# Board.net
KiCad netlist of a schematic drawn in EAGLE
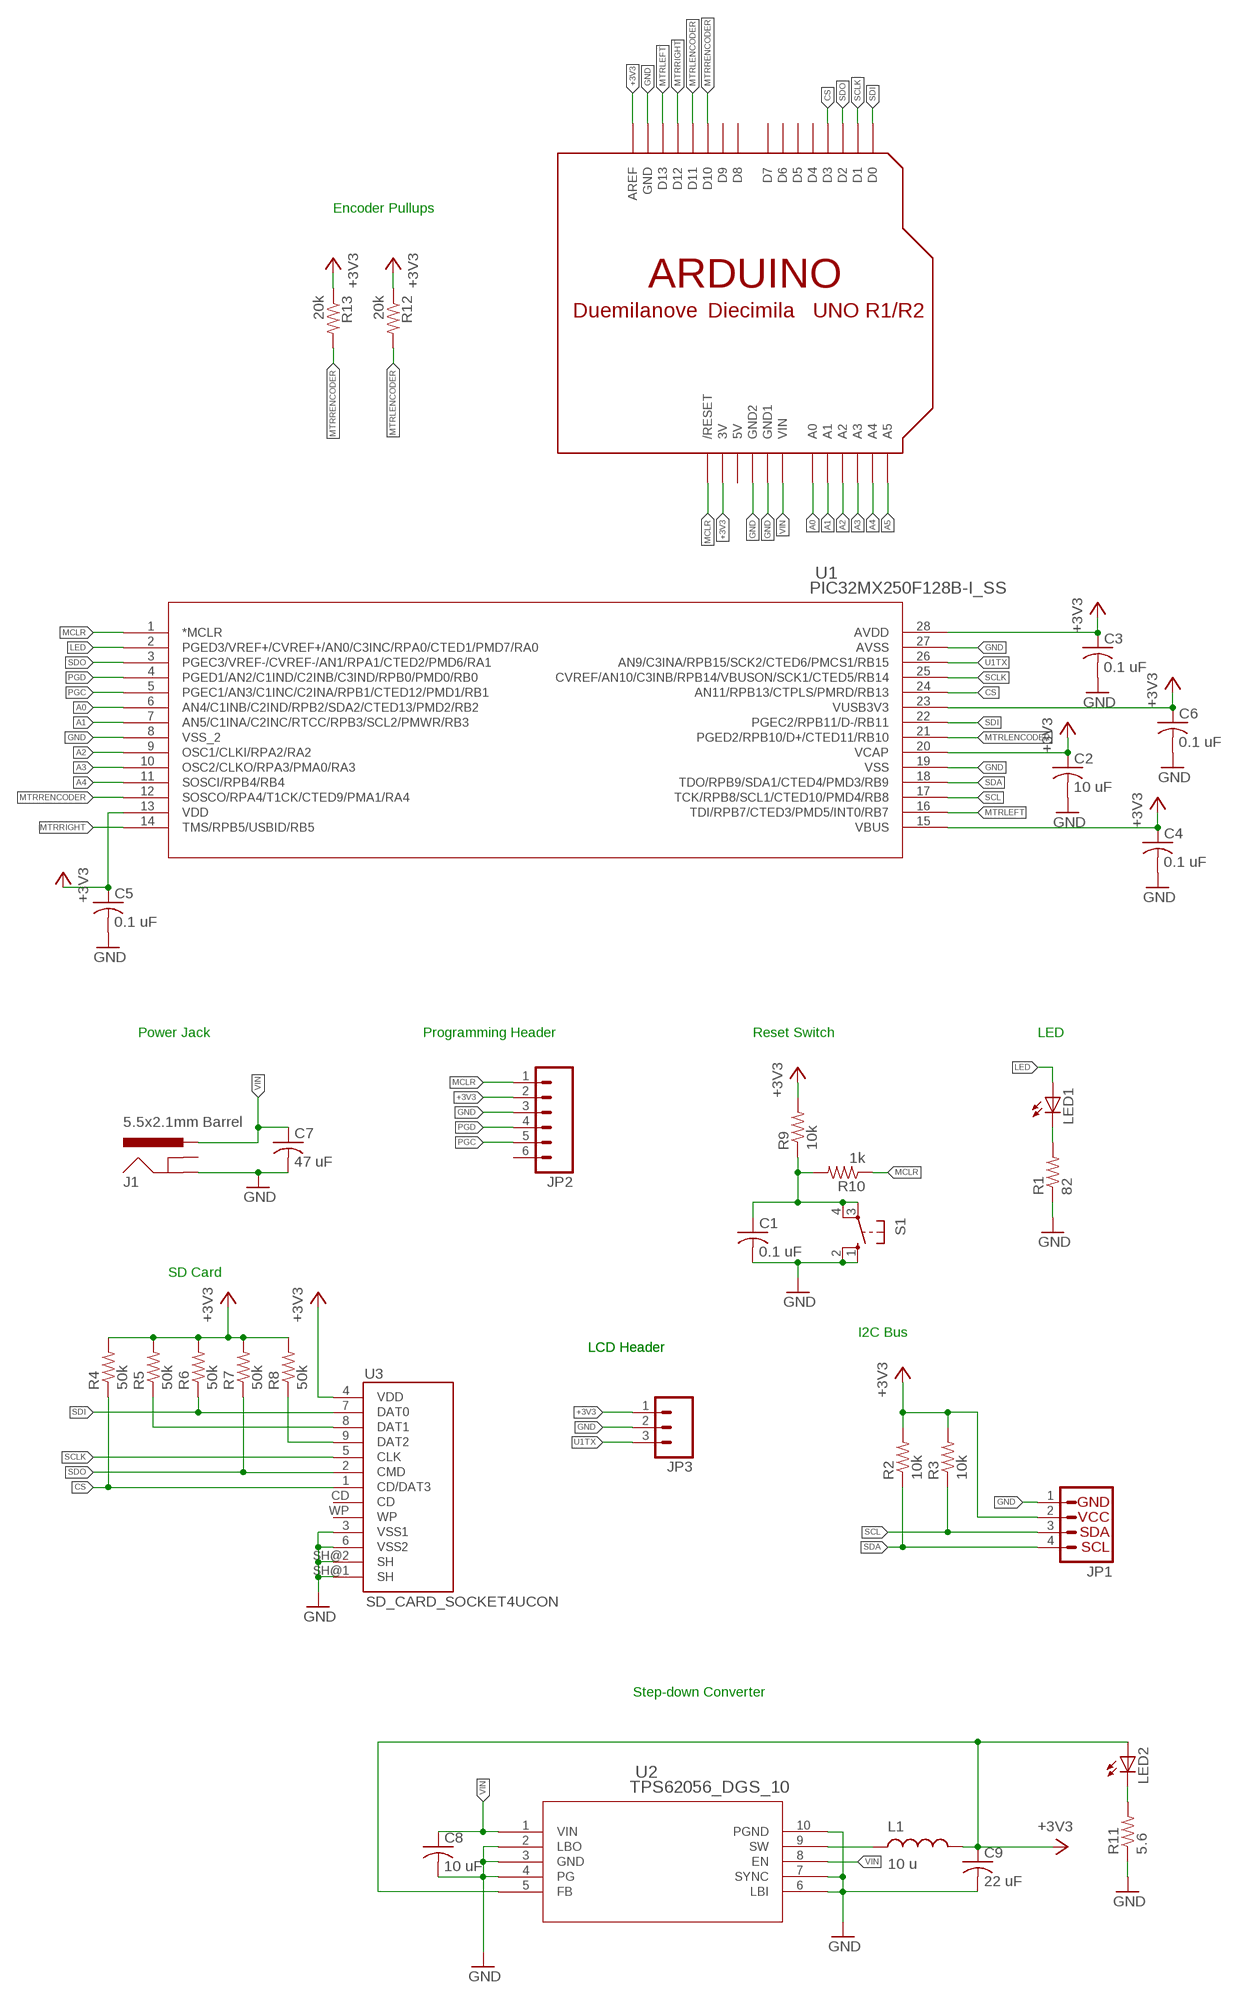
[diagram p0: schematic, sheet 1]

(export (version "E")
  (design (tool "Eeschema 10.0.6"))
  (components
    (comp (ref "C1")
      (value "0.1 uF")
      (footprint "eagle-import:C0805")
      (libsource (lib "eagle-import") (part "C-USC0805"))
    )
    (comp (ref "C2")
      (value "10 uF")
      (footprint "eagle-import:C0805")
      (libsource (lib "eagle-import") (part "C-USC0805"))
    )
    (comp (ref "C3")
      (value "0.1 uF")
      (footprint "eagle-import:C0805")
      (libsource (lib "eagle-import") (part "C-USC0805"))
    )
    (comp (ref "C4")
      (value "0.1 uF")
      (footprint "eagle-import:C0805")
      (libsource (lib "eagle-import") (part "C-USC0805"))
    )
    (comp (ref "C5")
      (value "0.1 uF")
      (footprint "eagle-import:C0805")
      (libsource (lib "eagle-import") (part "C-USC0805"))
    )
    (comp (ref "C6")
      (value "0.1 uF")
      (footprint "eagle-import:C0805")
      (libsource (lib "eagle-import") (part "C-USC0805"))
    )
    (comp (ref "C7")
      (value "47 uF")
      (footprint "eagle-import:C0805")
      (libsource (lib "eagle-import") (part "C-USC0805"))
    )
    (comp (ref "C8")
      (value "10 uF")
      (footprint "eagle-import:C0805")
      (libsource (lib "eagle-import") (part "C-USC0805"))
    )
    (comp (ref "C9")
      (value "22 uF")
      (footprint "eagle-import:C0805")
      (libsource (lib "eagle-import") (part "C-USC0805"))
    )
    (comp (ref "J1")
      (value "5.5x2.1mm Barrel")
      (footprint "eagle-import:POWER_JACK_SMD")
      (libsource (lib "eagle-import") (part "POWER_JACKSMD"))
    )
    (comp (ref "JP1")
      (value "I2C_STANDARD")
      (footprint "eagle-import:1X04")
      (libsource (lib "eagle-import") (part "I2C_STANDARD"))
    )
    (comp (ref "JP2")
      (value "M06SILK_FEMALE_PTH")
      (footprint "eagle-import:1X06")
      (libsource (lib "eagle-import") (part "M06SILK_FEMALE_PTH"))
    )
    (comp (ref "JP3")
      (value "M03PTH")
      (footprint "eagle-import:1X03")
      (libsource (lib "eagle-import") (part "M03PTH"))
    )
    (comp (ref "L1")
      (value "10 u")
      (footprint "eagle-import:SLF7032T-100M1R4-2PF")
      (libsource (lib "eagle-import") (part "SLF7032T-100M1R4-2PF"))
    )
    (comp (ref "LED1")
      (value "LEDCHIPLED_1206")
      (footprint "eagle-import:CHIPLED_1206")
      (libsource (lib "eagle-import") (part "LEDCHIPLED_1206"))
    )
    (comp (ref "LED2")
      (value "LEDCHIPLED_1206")
      (footprint "eagle-import:CHIPLED_1206")
      (libsource (lib "eagle-import") (part "LEDCHIPLED_1206"))
    )
    (comp (ref "R1")
      (value "82")
      (footprint "eagle-import:R1210W")
      (libsource (lib "eagle-import") (part "R-US_R1210W"))
    )
    (comp (ref "R2")
      (value "10k")
      (footprint "eagle-import:R0805W")
      (libsource (lib "eagle-import") (part "R-US_R0805W"))
    )
    (comp (ref "R3")
      (value "10k")
      (footprint "eagle-import:R0805W")
      (libsource (lib "eagle-import") (part "R-US_R0805W"))
    )
    (comp (ref "R4")
      (value "50k")
      (footprint "eagle-import:R0805W")
      (libsource (lib "eagle-import") (part "R-US_R0805W"))
    )
    (comp (ref "R5")
      (value "50k")
      (footprint "eagle-import:R0805W")
      (libsource (lib "eagle-import") (part "R-US_R0805W"))
    )
    (comp (ref "R6")
      (value "50k")
      (footprint "eagle-import:R0805W")
      (libsource (lib "eagle-import") (part "R-US_R0805W"))
    )
    (comp (ref "R7")
      (value "50k")
      (footprint "eagle-import:R0805W")
      (libsource (lib "eagle-import") (part "R-US_R0805W"))
    )
    (comp (ref "R8")
      (value "50k")
      (footprint "eagle-import:R0805W")
      (libsource (lib "eagle-import") (part "R-US_R0805W"))
    )
    (comp (ref "R9")
      (value "10k")
      (footprint "eagle-import:R0805W")
      (libsource (lib "eagle-import") (part "R-US_R0805W"))
    )
    (comp (ref "R10")
      (value "1k")
      (footprint "eagle-import:R0805W")
      (libsource (lib "eagle-import") (part "R-US_R0805W"))
    )
    (comp (ref "R11")
      (value "5.6")
      (footprint "eagle-import:R1210W")
      (libsource (lib "eagle-import") (part "R-US_R1210W"))
    )
    (comp (ref "R12")
      (value "20k")
      (footprint "eagle-import:R0805W")
      (libsource (lib "eagle-import") (part "R-US_R0805W"))
    )
    (comp (ref "R13")
      (value "20k")
      (footprint "eagle-import:R0805W")
      (libsource (lib "eagle-import") (part "R-US_R0805W"))
    )
    (comp (ref "S1")
      (value "10-XX")
      (footprint "eagle-import:B3F-10XX")
      (libsource (lib "eagle-import") (part "10-XX"))
    )
    (comp (ref "U$1")
      (value "ARDUINO-NOHOLE")
      (footprint "eagle-import:ARDUINO-NOHOLE")
      (libsource (lib "eagle-import") (part "ARDUINO-NOHOLE"))
    )
    (comp (ref "U1")
      (value "PIC32MX250F128B-I_SS")
      (footprint "eagle-import:SSOP28_MC")
      (libsource (lib "eagle-import") (part "PIC32MX250F128B-I_SS"))
    )
    (comp (ref "U2")
      (value "TPS62056_DGS_10")
      (footprint "eagle-import:DGS10")
      (fields
        (field (name "GENERIC_PART_NUMBER") "TPS62056")
        (field (name "MANUFACTURER") "Texas Instruments")
        (field (name "MANUFACTURER_PART_NUMBER") "tps62056_dgs_10")
      )
      (libsource (lib "eagle-import") (part "TPS62056_DGS_10"))
    )
    (comp (ref "U3")
      (value "SD_CARD_SOCKET4UCON")
      (footprint "eagle-import:SDCARD_4UCONN")
      (libsource (lib "eagle-import") (part "SD_CARD_SOCKET4UCON"))
    )
  )
  (nets
    (net (code "1") (name "+3V3") (class "Default")
      (node (ref "C2") (pin "1") (pinfunction "1_1") (pintype "passive"))
      (node (ref "C3") (pin "1") (pinfunction "1_1") (pintype "passive"))
      (node (ref "C4") (pin "1") (pinfunction "1_1") (pintype "passive"))
      (node (ref "C5") (pin "1") (pinfunction "1_1") (pintype "passive"))
      (node (ref "C6") (pin "1") (pinfunction "1_1") (pintype "passive"))
      (node (ref "C9") (pin "1") (pinfunction "1_1") (pintype "passive"))
      (node (ref "JP1") (pin "2") (pinfunction "2_2") (pintype "passive"))
      (node (ref "JP2") (pin "2") (pinfunction "2_2") (pintype "passive"))
      (node (ref "JP3") (pin "1") (pinfunction "1_1") (pintype "passive"))
      (node (ref "L1") (pin "P$2") (pinfunction "P$2_P$2") (pintype "bidirectional"))
      (node (ref "LED2") (pin "A") (pinfunction "A_A") (pintype "passive"))
      (node (ref "R12") (pin "1") (pinfunction "1_1") (pintype "passive"))
      (node (ref "R13") (pin "1") (pinfunction "1_1") (pintype "passive"))
      (node (ref "R2") (pin "2") (pinfunction "2_2") (pintype "passive"))
      (node (ref "R3") (pin "2") (pinfunction "2_2") (pintype "passive"))
      (node (ref "R4") (pin "2") (pinfunction "2_2") (pintype "passive"))
      (node (ref "R5") (pin "2") (pinfunction "2_2") (pintype "passive"))
      (node (ref "R6") (pin "2") (pinfunction "2_2") (pintype "passive"))
      (node (ref "R7") (pin "2") (pinfunction "2_2") (pintype "passive"))
      (node (ref "R8") (pin "2") (pinfunction "2_2") (pintype "passive"))
      (node (ref "R9") (pin "2") (pinfunction "2_2") (pintype "passive"))
      (node (ref "U$1") (pin "3V") (pinfunction "3V_3V") (pintype "power_in"))
      (node (ref "U$1") (pin "AREF") (pinfunction "AREF_AREF") (pintype "bidirectional"))
      (node (ref "U1") (pin "13") (pinfunction "VDD_13") (pintype "power_in"))
      (node (ref "U1") (pin "15") (pinfunction "VBUS_15") (pintype "power_in"))
      (node (ref "U1") (pin "20") (pinfunction "VCAP_20") (pintype "power_in"))
      (node (ref "U1") (pin "23") (pinfunction "VUSB3V3_23") (pintype "power_in"))
      (node (ref "U1") (pin "28") (pinfunction "AVDD_28") (pintype "power_in"))
      (node (ref "U2") (pin "5") (pinfunction "FB_5") (pintype "input"))
      (node (ref "U3") (pin "4") (pinfunction "VDD_4") (pintype "power_in"))
    )
    (net (code "2") (name "/5V") (class "Default")
      (node (ref "U$1") (pin "5V") (pinfunction "5V_5V") (pintype "power_in"))
    )
    (net (code "3") (name "A0") (class "Default")
      (node (ref "U$1") (pin "A0") (pinfunction "A0_A0") (pintype "bidirectional"))
      (node (ref "U1") (pin "6") (pinfunction "AN4/C1INB/C2IND/RPB2/SDA2/CTED13/PMD2/RB2_6") (pintype "bidirectional"))
    )
    (net (code "4") (name "A1") (class "Default")
      (node (ref "U$1") (pin "A1") (pinfunction "A1_A1") (pintype "bidirectional"))
      (node (ref "U1") (pin "7") (pinfunction "AN5/C1INA/C2INC/RTCC/RPB3/SCL2/PMWR/RB3_7") (pintype "bidirectional"))
    )
    (net (code "5") (name "A2") (class "Default")
      (node (ref "U$1") (pin "A2") (pinfunction "A2_A2") (pintype "bidirectional"))
      (node (ref "U1") (pin "9") (pinfunction "OSC1/CLKI/RPA2/RA2_9") (pintype "bidirectional"))
    )
    (net (code "6") (name "A3") (class "Default")
      (node (ref "U$1") (pin "A3") (pinfunction "A3_A3") (pintype "bidirectional"))
      (node (ref "U1") (pin "10") (pinfunction "OSC2/CLKO/RPA3/PMA0/RA3_10") (pintype "bidirectional"))
    )
    (net (code "7") (name "A4") (class "Default")
      (node (ref "U$1") (pin "A4") (pinfunction "A4_A4") (pintype "bidirectional"))
      (node (ref "U1") (pin "11") (pinfunction "SOSCI/RPB4/RB4_11") (pintype "bidirectional"))
    )
    (net (code "8") (name "A5") (class "Default")
      (node (ref "U$1") (pin "A5") (pinfunction "A5_A5") (pintype "bidirectional"))
    )
    (net (code "9") (name "CS") (class "Default")
      (node (ref "R4") (pin "1") (pinfunction "1_1") (pintype "passive"))
      (node (ref "U$1") (pin "D3") (pinfunction "D3_D3") (pintype "bidirectional"))
      (node (ref "U1") (pin "24") (pinfunction "AN11/RPB13/CTPLS/PMRD/RB13_24") (pintype "bidirectional"))
      (node (ref "U3") (pin "1") (pinfunction "CD/DAT3_1") (pintype "bidirectional"))
    )
    (net (code "10") (name "GND") (class "Default")
      (node (ref "C1") (pin "2") (pinfunction "2_2") (pintype "passive"))
      (node (ref "C2") (pin "2") (pinfunction "2_2") (pintype "passive"))
      (node (ref "C3") (pin "2") (pinfunction "2_2") (pintype "passive"))
      (node (ref "C4") (pin "2") (pinfunction "2_2") (pintype "passive"))
      (node (ref "C5") (pin "2") (pinfunction "2_2") (pintype "passive"))
      (node (ref "C6") (pin "2") (pinfunction "2_2") (pintype "passive"))
      (node (ref "C7") (pin "2") (pinfunction "2_2") (pintype "passive"))
      (node (ref "C8") (pin "2") (pinfunction "2_2") (pintype "passive"))
      (node (ref "C9") (pin "2") (pinfunction "2_2") (pintype "passive"))
      (node (ref "J1") (pin "P$4") (pinfunction "GND_P$4") (pintype "bidirectional"))
      (node (ref "JP1") (pin "1") (pinfunction "1_1") (pintype "passive"))
      (node (ref "JP2") (pin "3") (pinfunction "3_3") (pintype "passive"))
      (node (ref "JP3") (pin "2") (pinfunction "2_2") (pintype "passive"))
      (node (ref "R1") (pin "1") (pinfunction "1_1") (pintype "passive"))
      (node (ref "R11") (pin "1") (pinfunction "1_1") (pintype "passive"))
      (node (ref "S1") (pin "1") (pinfunction "S_1") (pintype "passive"))
      (node (ref "S1") (pin "2") (pinfunction "S1_2") (pintype "passive"))
      (node (ref "U$1") (pin "GND") (pinfunction "GND_GND") (pintype "power_in"))
      (node (ref "U$1") (pin "GND1") (pinfunction "GND1_GND1") (pintype "power_in"))
      (node (ref "U$1") (pin "GND2") (pinfunction "GND2_GND2") (pintype "power_in"))
      (node (ref "U1") (pin "19") (pinfunction "VSS_19") (pintype "power_in"))
      (node (ref "U1") (pin "27") (pinfunction "AVSS_27") (pintype "power_in"))
      (node (ref "U1") (pin "8") (pinfunction "VSS_2_8") (pintype "power_in"))
      (node (ref "U2") (pin "10") (pinfunction "PGND_10") (pintype "input"))
      (node (ref "U2") (pin "2") (pinfunction "LBO_2") (pintype "output"))
      (node (ref "U2") (pin "3") (pinfunction "GND_3") (pintype "input"))
      (node (ref "U2") (pin "4") (pinfunction "PG_4") (pintype "output"))
      (node (ref "U2") (pin "6") (pinfunction "LBI_6") (pintype "input"))
      (node (ref "U2") (pin "7") (pinfunction "SYNC_7") (pintype "input"))
      (node (ref "U3") (pin "3") (pinfunction "VSS1_3") (pintype "power_in"))
      (node (ref "U3") (pin "6") (pinfunction "VSS2_6") (pintype "power_in"))
      (node (ref "U3") (pin "SH@1") (pinfunction "SH_SH@1") (pintype "bidirectional"))
      (node (ref "U3") (pin "SH@2") (pinfunction "SH_SH@2") (pintype "bidirectional"))
    )
    (net (code "11") (name "LED") (class "Default")
      (node (ref "LED1") (pin "A") (pinfunction "A_A") (pintype "passive"))
      (node (ref "U1") (pin "2") (pinfunction "PGED3/VREF+/CVREF+/AN0/C3INC/RPA0/CTED1/PMD7/RA0_2") (pintype "bidirectional"))
    )
    (net (code "12") (name "MCLR") (class "Default")
      (node (ref "JP2") (pin "1") (pinfunction "1_1") (pintype "passive"))
      (node (ref "R10") (pin "1") (pinfunction "1_1") (pintype "passive"))
      (node (ref "U$1") (pin "RESET") (pinfunction "/RESET_RESET") (pintype "bidirectional"))
      (node (ref "U1") (pin "1") (pinfunction "*MCLR_1") (pintype "input"))
    )
    (net (code "13") (name "MTRLEFT") (class "Default")
      (node (ref "U$1") (pin "D13") (pinfunction "D13_D13") (pintype "bidirectional"))
      (node (ref "U1") (pin "16") (pinfunction "TDI/RPB7/CTED3/PMD5/INT0/RB7_16") (pintype "bidirectional"))
    )
    (net (code "14") (name "MTRLENCODER") (class "Default")
      (node (ref "R12") (pin "2") (pinfunction "2_2") (pintype "passive"))
      (node (ref "U$1") (pin "D11") (pinfunction "D11_D11") (pintype "bidirectional"))
      (node (ref "U1") (pin "21") (pinfunction "PGED2/RPB10/D+/CTED11/RB10_21") (pintype "bidirectional"))
    )
    (net (code "15") (name "MTRRENCODER") (class "Default")
      (node (ref "R13") (pin "2") (pinfunction "2_2") (pintype "passive"))
      (node (ref "U$1") (pin "D10") (pinfunction "D10_D10") (pintype "bidirectional"))
      (node (ref "U1") (pin "12") (pinfunction "SOSCO/RPA4/T1CK/CTED9/PMA1/RA4_12") (pintype "bidirectional"))
    )
    (net (code "16") (name "MTRRIGHT") (class "Default")
      (node (ref "U$1") (pin "D12") (pinfunction "D12_D12") (pintype "bidirectional"))
      (node (ref "U1") (pin "14") (pinfunction "TMS/RPB5/USBID/RB5_14") (pintype "bidirectional"))
    )
    (net (code "17") (name "Net-(LED1-PadC)") (class "Default")
      (node (ref "LED1") (pin "C") (pinfunction "C_C") (pintype "passive"))
      (node (ref "R1") (pin "2") (pinfunction "2_2") (pintype "passive"))
    )
    (net (code "18") (name "Net-(LED2-PadC)") (class "Default")
      (node (ref "LED2") (pin "C") (pinfunction "C_C") (pintype "passive"))
      (node (ref "R11") (pin "2") (pinfunction "2_2") (pintype "passive"))
    )
    (net (code "19") (name "Net-(S1-P)") (class "Default")
      (node (ref "C1") (pin "1") (pinfunction "1_1") (pintype "passive"))
      (node (ref "R10") (pin "2") (pinfunction "2_2") (pintype "passive"))
      (node (ref "R9") (pin "1") (pinfunction "1_1") (pintype "passive"))
      (node (ref "S1") (pin "3") (pinfunction "P_3") (pintype "passive"))
      (node (ref "S1") (pin "4") (pinfunction "P1_4") (pintype "passive"))
    )
    (net (code "20") (name "Net-(U2-SW)") (class "Default")
      (node (ref "L1") (pin "P$1") (pinfunction "P$1_P$1") (pintype "bidirectional"))
      (node (ref "U2") (pin "9") (pinfunction "SW_9") (pintype "output"))
    )
    (net (code "21") (name "Net-(U3-DAT1)") (class "Default")
      (node (ref "R5") (pin "1") (pinfunction "1_1") (pintype "passive"))
      (node (ref "U3") (pin "8") (pinfunction "DAT1_8") (pintype "bidirectional"))
    )
    (net (code "22") (name "Net-(U3-DAT2)") (class "Default")
      (node (ref "R8") (pin "1") (pinfunction "1_1") (pintype "passive"))
      (node (ref "U3") (pin "9") (pinfunction "DAT2_9") (pintype "bidirectional"))
    )
    (net (code "23") (name "PGC") (class "Default")
      (node (ref "JP2") (pin "5") (pinfunction "5_5") (pintype "passive"))
      (node (ref "U1") (pin "5") (pinfunction "PGEC1/AN3/C1INC/C2INA/RPB1/CTED12/PMD1/RB1_5") (pintype "bidirectional"))
    )
    (net (code "24") (name "PGD") (class "Default")
      (node (ref "JP2") (pin "4") (pinfunction "4_4") (pintype "passive"))
      (node (ref "U1") (pin "4") (pinfunction "PGED1/AN2/C1IND/C2INB/C3IND/RPB0/PMD0/RB0_4") (pintype "bidirectional"))
    )
    (net (code "25") (name "SCL") (class "Default")
      (node (ref "JP1") (pin "3") (pinfunction "3_3") (pintype "passive"))
      (node (ref "R3") (pin "1") (pinfunction "1_1") (pintype "passive"))
      (node (ref "U1") (pin "17") (pinfunction "TCK/RPB8/SCL1/CTED10/PMD4/RB8_17") (pintype "bidirectional"))
    )
    (net (code "26") (name "SCLK") (class "Default")
      (node (ref "U$1") (pin "D1") (pinfunction "D1_D1") (pintype "bidirectional"))
      (node (ref "U1") (pin "25") (pinfunction "CVREF/AN10/C3INB/RPB14/VBUSON/SCK1/CTED5/RB14_25") (pintype "bidirectional"))
      (node (ref "U3") (pin "5") (pinfunction "CLK_5") (pintype "bidirectional"))
    )
    (net (code "27") (name "SDA") (class "Default")
      (node (ref "JP1") (pin "4") (pinfunction "4_4") (pintype "passive"))
      (node (ref "R2") (pin "1") (pinfunction "1_1") (pintype "passive"))
      (node (ref "U1") (pin "18") (pinfunction "TDO/RPB9/SDA1/CTED4/PMD3/RB9_18") (pintype "bidirectional"))
    )
    (net (code "28") (name "SDI") (class "Default")
      (node (ref "R6") (pin "1") (pinfunction "1_1") (pintype "passive"))
      (node (ref "U$1") (pin "D0") (pinfunction "D0_D0") (pintype "bidirectional"))
      (node (ref "U1") (pin "22") (pinfunction "PGEC2/RPB11/D-/RB11_22") (pintype "bidirectional"))
      (node (ref "U3") (pin "7") (pinfunction "DAT0_7") (pintype "bidirectional"))
    )
    (net (code "29") (name "SDO") (class "Default")
      (node (ref "R7") (pin "1") (pinfunction "1_1") (pintype "passive"))
      (node (ref "U$1") (pin "D2") (pinfunction "D2_D2") (pintype "bidirectional"))
      (node (ref "U1") (pin "3") (pinfunction "PGEC3/VREF-/CVREF-/AN1/RPA1/CTED2/PMD6/RA1_3") (pintype "bidirectional"))
      (node (ref "U3") (pin "2") (pinfunction "CMD_2") (pintype "bidirectional"))
    )
    (net (code "30") (name "U1TX") (class "Default")
      (node (ref "JP3") (pin "3") (pinfunction "3_3") (pintype "passive"))
      (node (ref "U1") (pin "26") (pinfunction "AN9/C3INA/RPB15/SCK2/CTED6/PMCS1/RB15_26") (pintype "bidirectional"))
    )
    (net (code "31") (name "VIN") (class "Default")
      (node (ref "C7") (pin "1") (pinfunction "1_1") (pintype "passive"))
      (node (ref "C8") (pin "1") (pinfunction "1_1") (pintype "passive"))
      (node (ref "J1") (pin "VIN0") (pinfunction "PWR_VIN0") (pintype "bidirectional"))
      (node (ref "U$1") (pin "VIN") (pinfunction "VIN_VIN") (pintype "power_in"))
      (node (ref "U2") (pin "1") (pinfunction "VIN_1") (pintype "input"))
      (node (ref "U2") (pin "8") (pinfunction "EN_8") (pintype "input"))
    )
    (net (code "32") (name "unconnected-(J1-GNDBREAK-PadGND)") (class "Default")
      (node (ref "J1") (pin "GND") (pinfunction "GNDBREAK_GND") (pintype "bidirectional"))
    )
    (net (code "33") (name "unconnected-(JP2-Pad6)") (class "Default")
      (node (ref "JP2") (pin "6") (pinfunction "6_6") (pintype "passive"))
    )
    (net (code "34") (name "unconnected-(U$1-PadD4)") (class "Default")
      (node (ref "U$1") (pin "D4") (pinfunction "D4_D4") (pintype "bidirectional"))
    )
    (net (code "35") (name "unconnected-(U$1-PadD5)") (class "Default")
      (node (ref "U$1") (pin "D5") (pinfunction "D5_D5") (pintype "bidirectional"))
    )
    (net (code "36") (name "unconnected-(U$1-PadD6)") (class "Default")
      (node (ref "U$1") (pin "D6") (pinfunction "D6_D6") (pintype "bidirectional"))
    )
    (net (code "37") (name "unconnected-(U$1-PadD7)") (class "Default")
      (node (ref "U$1") (pin "D7") (pinfunction "D7_D7") (pintype "bidirectional"))
    )
    (net (code "38") (name "unconnected-(U$1-PadD8)") (class "Default")
      (node (ref "U$1") (pin "D8") (pinfunction "D8_D8") (pintype "bidirectional"))
    )
    (net (code "39") (name "unconnected-(U$1-PadD9)") (class "Default")
      (node (ref "U$1") (pin "D9") (pinfunction "D9_D9") (pintype "bidirectional"))
    )
    (net (code "40") (name "unconnected-(U3-PadCD)") (class "Default")
      (node (ref "U3") (pin "CD") (pinfunction "CD_CD") (pintype "bidirectional"))
    )
    (net (code "41") (name "unconnected-(U3-PadWP)") (class "Default")
      (node (ref "U3") (pin "WP") (pinfunction "WP_WP") (pintype "bidirectional"))
    )
  )
)
